# 22VPowerBoard.net
KiCad netlist of a schematic drawn in EAGLE
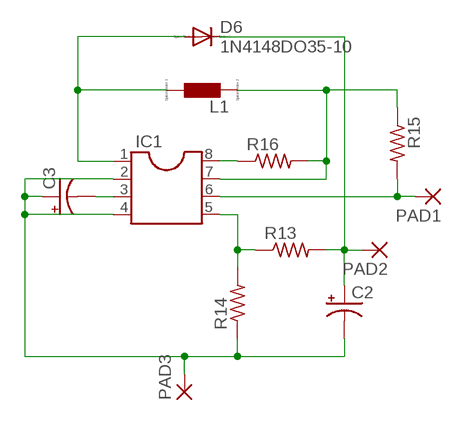
[diagram p0: schematic, sheet 1]

(export (version "E")
  (design (tool "Eeschema 10.0.6"))
  (components
    (comp (ref "C2")
      (value "CPOL-USE2.5-7")
      (footprint "eagle-import:E2,5-7")
      (libsource (lib "eagle-import") (part "CPOL-USE2.5-7"))
    )
    (comp (ref "C3")
      (value "CPOL-USE2.5-7")
      (footprint "eagle-import:E2,5-7")
      (libsource (lib "eagle-import") (part "CPOL-USE2.5-7"))
    )
    (comp (ref "D6")
      (value "1N4148DO35-10")
      (footprint "eagle-import:DO35-10")
      (libsource (lib "eagle-import") (part "1N4148DO35-10"))
    )
    (comp (ref "IC1")
      (value "DIL8")
      (footprint "eagle-import:DIL08")
      (libsource (lib "eagle-import") (part "DIL8"))
    )
    (comp (ref "L1")
      (value "L0207/10")
      (footprint "eagle-import:0207_10")
      (libsource (lib "eagle-import") (part "L0207/10"))
    )
    (comp (ref "PAD1")
      (value "3,81/1,4")
      (footprint "eagle-import:3,81_1,4")
      (libsource (lib "eagle-import") (part "3,81/1,4"))
    )
    (comp (ref "PAD2")
      (value "3,81/1,4")
      (footprint "eagle-import:3,81_1,4")
      (libsource (lib "eagle-import") (part "3,81/1,4"))
    )
    (comp (ref "PAD3")
      (value "3,81/1,4")
      (footprint "eagle-import:3,81_1,4")
      (libsource (lib "eagle-import") (part "3,81/1,4"))
    )
    (comp (ref "R13")
      (value "R-US_0207/7")
      (footprint "eagle-import:0207_7")
      (libsource (lib "eagle-import") (part "R-US_0207/7"))
    )
    (comp (ref "R14")
      (value "R-US_0207/7")
      (footprint "eagle-import:0207_7")
      (libsource (lib "eagle-import") (part "R-US_0207/7"))
    )
    (comp (ref "R15")
      (value "R-US_0207/7")
      (footprint "eagle-import:0207_7")
      (libsource (lib "eagle-import") (part "R-US_0207/7"))
    )
    (comp (ref "R16")
      (value "R-US_0207/7")
      (footprint "eagle-import:0207_7")
      (libsource (lib "eagle-import") (part "R-US_0207/7"))
    )
  )
  (nets
    (net (code "1") (name "Net-(C3-Pad-)") (class "Default")
      (node (ref "C3") (pin "-") (pinfunction "-_-") (pintype "passive"))
      (node (ref "IC1") (pin "3") (pinfunction "3_3") (pintype "passive"))
    )
    (net (code "2") (name "Net-(D6-PadA)") (class "Default")
      (node (ref "D6") (pin "A") (pinfunction "A_A") (pintype "passive"))
      (node (ref "IC1") (pin "1") (pinfunction "1_1") (pintype "passive"))
      (node (ref "L1") (pin "1") (pinfunction "1_1") (pintype "passive"))
    )
    (net (code "3") (name "Net-(IC1-Pad5)") (class "Default")
      (node (ref "IC1") (pin "5") (pinfunction "5_5") (pintype "passive"))
      (node (ref "R13") (pin "1") (pinfunction "1_1") (pintype "passive"))
      (node (ref "R14") (pin "2") (pinfunction "2_2") (pintype "passive"))
    )
    (net (code "4") (name "Net-(IC1-Pad7)") (class "Default")
      (node (ref "IC1") (pin "7") (pinfunction "7_7") (pintype "passive"))
      (node (ref "L1") (pin "2") (pinfunction "2_2") (pintype "passive"))
      (node (ref "R15") (pin "1") (pinfunction "1_1") (pintype "passive"))
      (node (ref "R16") (pin "2") (pinfunction "2_2") (pintype "passive"))
    )
    (net (code "5") (name "Net-(IC1-Pad8)") (class "Default")
      (node (ref "IC1") (pin "8") (pinfunction "8_8") (pintype "passive"))
      (node (ref "R16") (pin "1") (pinfunction "1_1") (pintype "passive"))
    )
    (net (code "6") (name "Net-(PAD1-P)") (class "Default")
      (node (ref "IC1") (pin "6") (pinfunction "6_6") (pintype "passive"))
      (node (ref "PAD1") (pin "1") (pinfunction "P_1") (pintype "passive"))
      (node (ref "R15") (pin "2") (pinfunction "2_2") (pintype "passive"))
    )
    (net (code "7") (name "Net-(PAD2-P)") (class "Default")
      (node (ref "C2") (pin "+") (pinfunction "+_+") (pintype "passive"))
      (node (ref "D6") (pin "C") (pinfunction "C_C") (pintype "passive"))
      (node (ref "PAD2") (pin "1") (pinfunction "P_1") (pintype "passive"))
      (node (ref "R13") (pin "2") (pinfunction "2_2") (pintype "passive"))
    )
    (net (code "8") (name "Net-(PAD3-P)") (class "Default")
      (node (ref "C2") (pin "-") (pinfunction "-_-") (pintype "passive"))
      (node (ref "C3") (pin "+") (pinfunction "+_+") (pintype "passive"))
      (node (ref "IC1") (pin "2") (pinfunction "2_2") (pintype "passive"))
      (node (ref "IC1") (pin "4") (pinfunction "4_4") (pintype "passive"))
      (node (ref "PAD3") (pin "1") (pinfunction "P_1") (pintype "passive"))
      (node (ref "R14") (pin "1") (pinfunction "1_1") (pintype "passive"))
    )
  )
)
